# Schematic.net
KiCad netlist of a schematic drawn in EAGLE
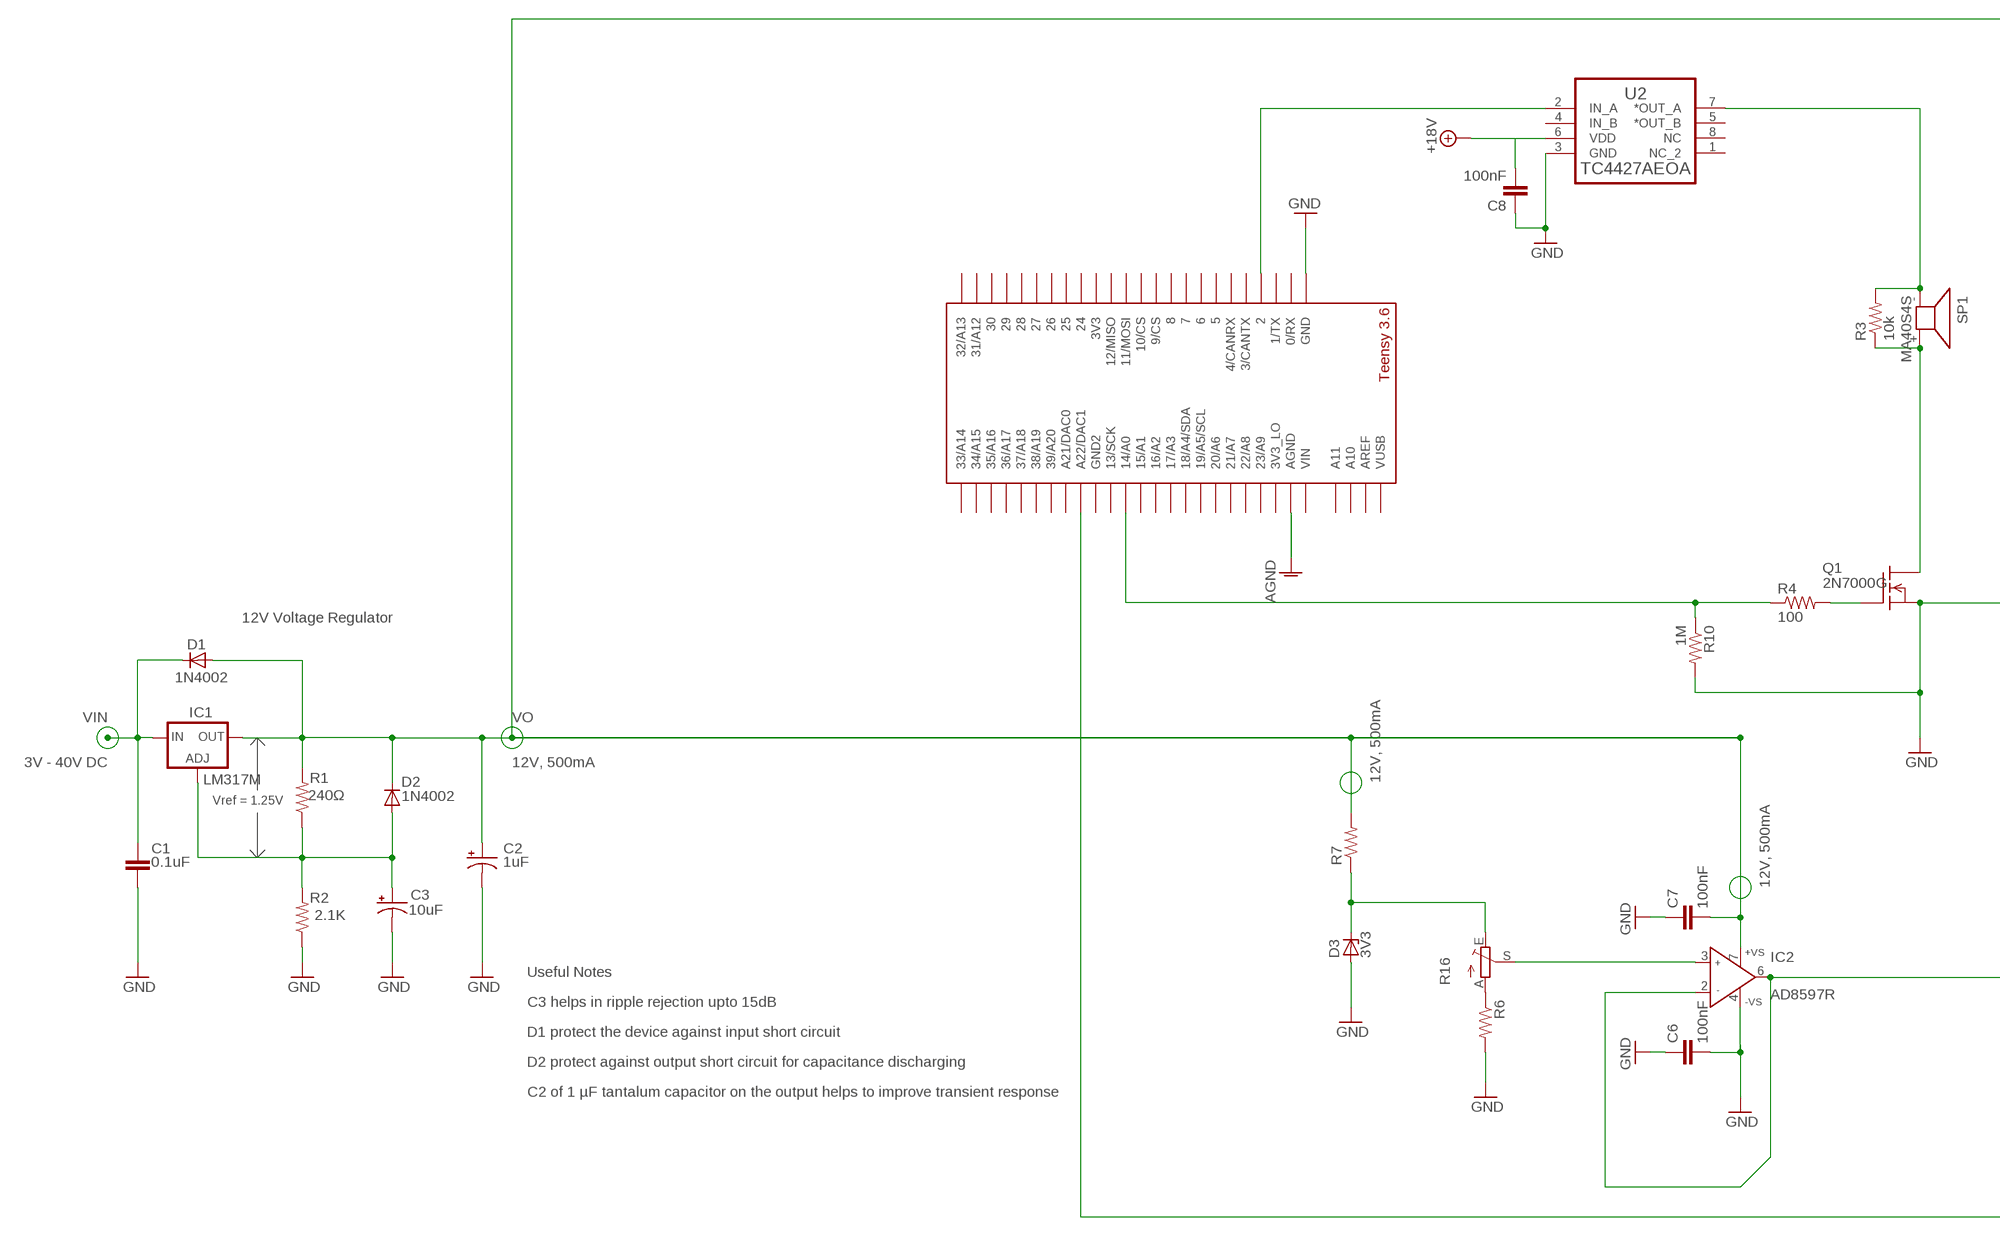
[diagram p0: schematic, sheet 1, part 1 of 2]
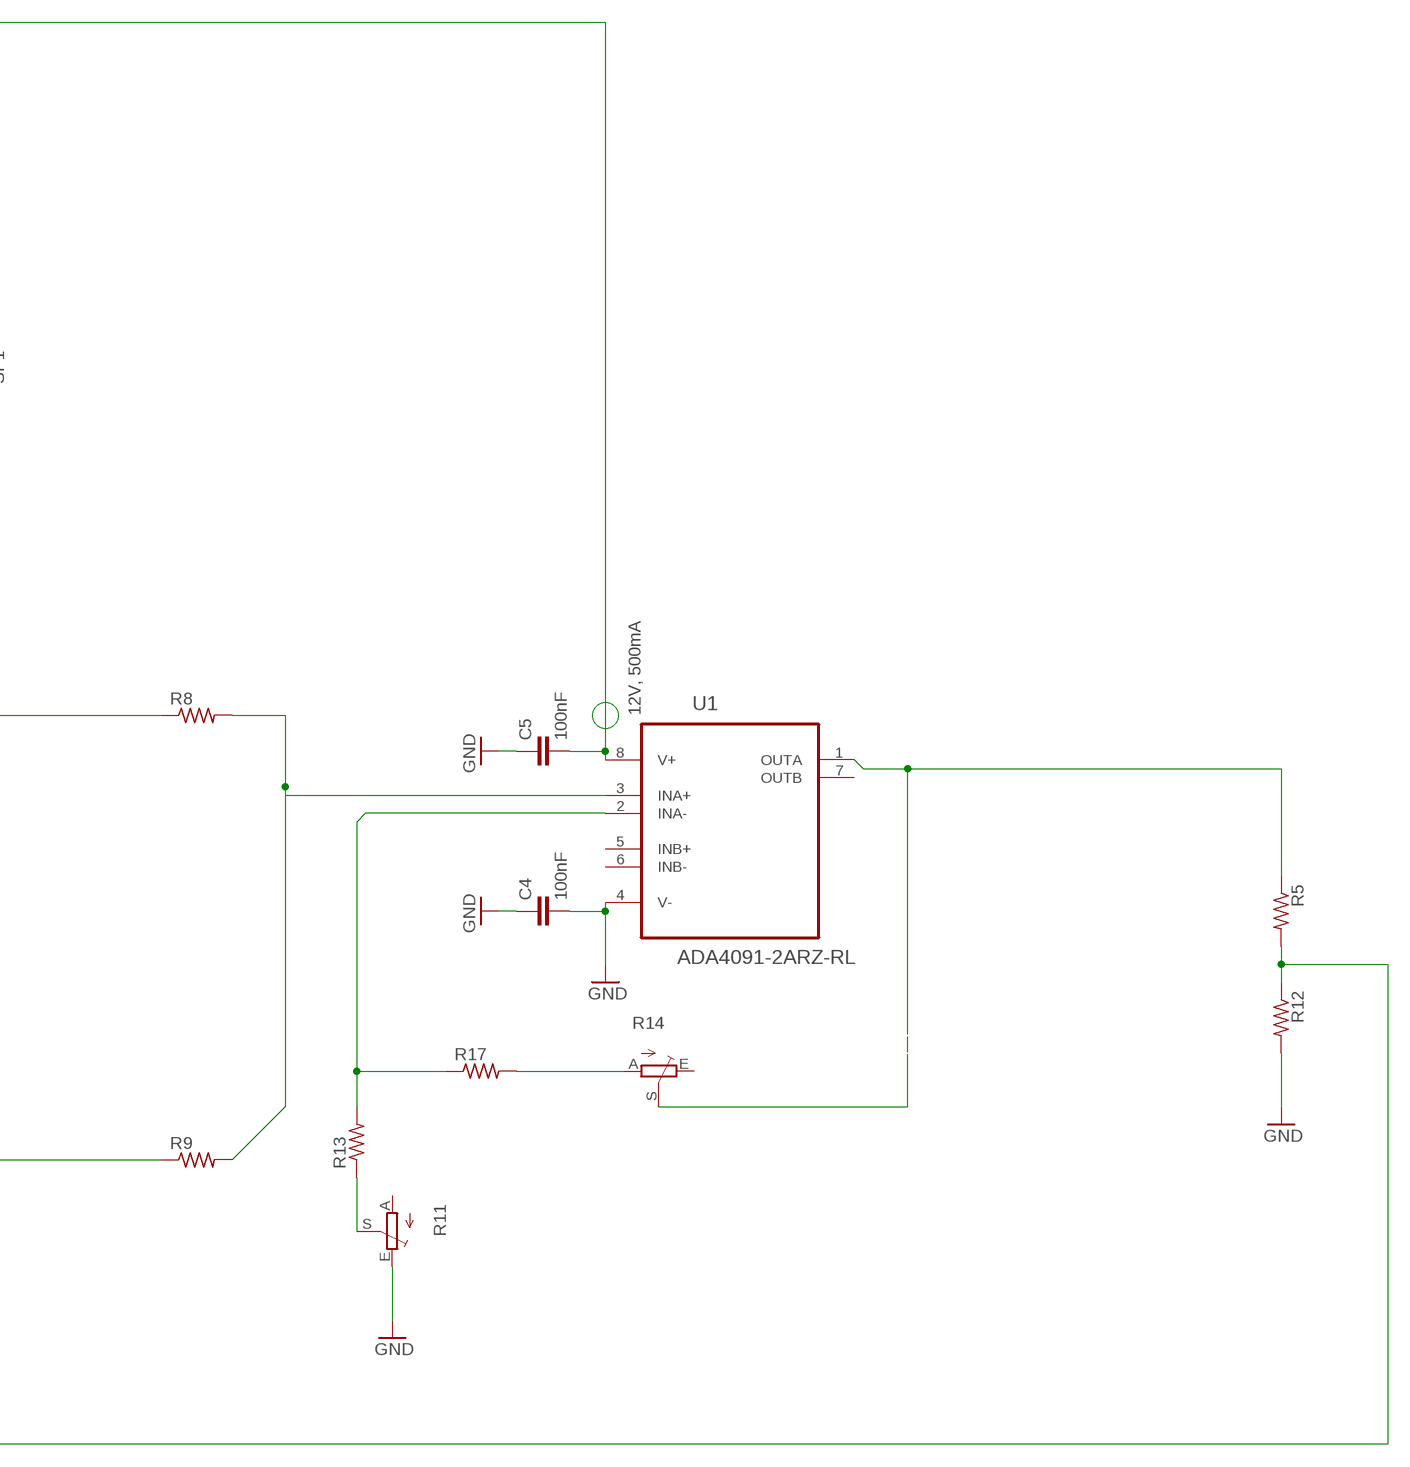
[diagram p1: schematic, sheet 1, part 2 of 2]

(export (version "E")
  (design (tool "Eeschema 10.0.6"))
  (components
    (comp (ref "C1")
      (value "0.1uF")
      (footprint "eagle-import:C075-052X106")
      (libsource (lib "eagle-import") (part "C-EU075-052X106"))
    )
    (comp (ref "C2")
      (value "1uF")
      (footprint "eagle-import:085CS_1AR")
      (libsource (lib "eagle-import") (part "CPOL-US085CS-1AR"))
    )
    (comp (ref "C3")
      (value "10uF")
      (footprint "eagle-import:085CS_1AR")
      (libsource (lib "eagle-import") (part "CPOL-US085CS-1AR"))
    )
    (comp (ref "C4")
      (value "100nF")
      (footprint "eagle-import:C2.5-3")
      (libsource (lib "eagle-import") (part "C2,5-3"))
    )
    (comp (ref "C5")
      (value "100nF")
      (footprint "eagle-import:C2.5-3")
      (libsource (lib "eagle-import") (part "C2,5-3"))
    )
    (comp (ref "C6")
      (value "100nF")
      (footprint "eagle-import:C2.5-3")
      (libsource (lib "eagle-import") (part "C2,5-3"))
    )
    (comp (ref "C7")
      (value "100nF")
      (footprint "eagle-import:C2.5-3")
      (libsource (lib "eagle-import") (part "C2,5-3"))
    )
    (comp (ref "C8")
      (value "100nF")
      (footprint "eagle-import:C2.5-3")
      (libsource (lib "eagle-import") (part "C2,5-3"))
    )
    (comp (ref "D1")
      (value "1N4002")
      (footprint "eagle-import:DO41-10")
      (libsource (lib "eagle-import") (part "1N4004"))
    )
    (comp (ref "D2")
      (value "1N4002")
      (footprint "eagle-import:DO41-10")
      (libsource (lib "eagle-import") (part "1N4004"))
    )
    (comp (ref "D3")
      (value "3V3")
      (footprint "eagle-import:DO41Z10")
      (libsource (lib "eagle-import") (part "1N4728"))
    )
    (comp (ref "IC1")
      (value "LM317MBSTT3")
      (footprint "eagle-import:SOT223")
      (fields (field (name "PARTNUMBER") "LM317M"))
      (libsource (lib "eagle-import") (part "LM317?MBSTT3"))
    )
    (comp (ref "IC2")
      (value "AD8597R")
      (footprint "eagle-import:SO8")
      (fields (field (name "MPN") "AD8597ARZ"))
      (libsource (lib "eagle-import") (part "AD8597R"))
    )
    (comp (ref "Q1")
      (value "2N7000G")
      (footprint "eagle-import:TO92-INLINE")
      (fields (field (name "MF") "Microchip") (field (name "MP") "2N7000-G"))
      (libsource (lib "eagle-import") (part "2N7000G"))
    )
    (comp (ref "R1")
      (value "240Ω")
      (footprint "eagle-import:M0805")
      (libsource (lib "eagle-import") (part "R-US_M0805"))
    )
    (comp (ref "R2")
      (value "2.1K")
      (footprint "eagle-import:M0805")
      (libsource (lib "eagle-import") (part "R-US_M0805"))
    )
    (comp (ref "R3")
      (value "10k")
      (footprint "eagle-import:R0805")
      (libsource (lib "eagle-import") (part "R-US_R0805"))
    )
    (comp (ref "R4")
      (value "100")
      (footprint "eagle-import:M0805")
      (libsource (lib "eagle-import") (part "R-US_M0805"))
    )
    (comp (ref "R5")
      (value "R-US_M0805")
      (footprint "eagle-import:M0805")
      (libsource (lib "eagle-import") (part "R-US_M0805"))
    )
    (comp (ref "R6")
      (value "R-US_M0805")
      (footprint "eagle-import:M0805")
      (libsource (lib "eagle-import") (part "R-US_M0805"))
    )
    (comp (ref "R7")
      (value "R-US_M0805")
      (footprint "eagle-import:M0805")
      (libsource (lib "eagle-import") (part "R-US_M0805"))
    )
    (comp (ref "R8")
      (value "R-US_M0805")
      (footprint "eagle-import:M0805")
      (libsource (lib "eagle-import") (part "R-US_M0805"))
    )
    (comp (ref "R9")
      (value "R-US_M0805")
      (footprint "eagle-import:M0805")
      (libsource (lib "eagle-import") (part "R-US_M0805"))
    )
    (comp (ref "R10")
      (value "1M")
      (footprint "eagle-import:M0805")
      (libsource (lib "eagle-import") (part "R-US_M0805"))
    )
    (comp (ref "R11")
      (value "TRIM_EU-CA6V")
      (footprint "eagle-import:CA6V")
      (libsource (lib "eagle-import") (part "TRIM_EU-CA6V"))
    )
    (comp (ref "R12")
      (value "R-US_M0805")
      (footprint "eagle-import:M0805")
      (libsource (lib "eagle-import") (part "R-US_M0805"))
    )
    (comp (ref "R13")
      (value "R-US_M0805")
      (footprint "eagle-import:M0805")
      (libsource (lib "eagle-import") (part "R-US_M0805"))
    )
    (comp (ref "R14")
      (value "TRIM_EU-CA6V")
      (footprint "eagle-import:CA6V")
      (libsource (lib "eagle-import") (part "TRIM_EU-CA6V"))
    )
    (comp (ref "R16")
      (value "TRIM_EU-CA6V")
      (footprint "eagle-import:CA6V")
      (libsource (lib "eagle-import") (part "TRIM_EU-CA6V"))
    )
    (comp (ref "R17")
      (value "R-US_M0805")
      (footprint "eagle-import:M0805")
      (libsource (lib "eagle-import") (part "R-US_M0805"))
    )
    (comp (ref "SP1")
      (value "MA40S4S")
      (footprint "eagle-import:MA40")
      (libsource (lib "eagle-import") (part "MA40S4S"))
    )
    (comp (ref "U$1")
      (value "TEENSY_3.5/3.6_BASIC")
      (footprint "eagle-import:TEENSY_3.5_3.6_BASIC")
      (libsource (lib "eagle-import") (part "TEENSY_3.5/3.6_BASIC"))
    )
    (comp (ref "U1")
      (value "ADA4091-2ARZ-RL")
      (footprint "eagle-import:SOIC127P600X175-8N")
      (fields (field (name "MF") "Analog"))
      (libsource (lib "eagle-import") (part "ADA4091-2ARZ-RL"))
    )
    (comp (ref "U2")
      (value "TC4427AEOA")
      (footprint "eagle-import:SOIC127P600X175-8N")
      (libsource (lib "eagle-import") (part "TC4427AEOA"))
    )
  )
  (nets
    (net (code "1") (name "+18V") (class "Default")
      (node (ref "U2") (pin "6") (pinfunction "VDD_6") (pintype "power_in"))
    )
    (net (code "2") (name "/VIN") (class "Default")
      (node (ref "C1") (pin "1") (pinfunction "1_1") (pintype "passive"))
      (node (ref "D1") (pin "C") (pinfunction "C_C") (pintype "passive"))
      (node (ref "IC1") (pin "3") (pinfunction "IN_3") (pintype "input"))
    )
    (net (code "3") (name "/VO") (class "Default")
      (node (ref "C2") (pin "+") (pinfunction "+_+") (pintype "passive"))
      (node (ref "C5") (pin "2") (pinfunction "2_2") (pintype "passive"))
      (node (ref "C7") (pin "2") (pinfunction "2_2") (pintype "passive"))
      (node (ref "D1") (pin "A") (pinfunction "A_A") (pintype "passive"))
      (node (ref "D2") (pin "C") (pinfunction "C_C") (pintype "passive"))
      (node (ref "IC1") (pin "4") (pinfunction "OUT_4") (pintype "passive"))
      (node (ref "IC2") (pin "7") (pinfunction "+VS_7") (pintype "input"))
      (node (ref "R1") (pin "2") (pinfunction "2_2") (pintype "passive"))
      (node (ref "R7") (pin "2") (pinfunction "2_2") (pintype "passive"))
      (node (ref "U1") (pin "8") (pinfunction "V+_8") (pintype "power_in"))
    )
    (net (code "4") (name "AGND") (class "Default")
      (node (ref "U$1") (pin "AGND") (pinfunction "AGND_AGND") (pintype "bidirectional"))
    )
    (net (code "5") (name "GND") (class "Default")
      (node (ref "C1") (pin "2") (pinfunction "2_2") (pintype "passive"))
      (node (ref "C2") (pin "-") (pinfunction "-_-") (pintype "passive"))
      (node (ref "C3") (pin "-") (pinfunction "-_-") (pintype "passive"))
      (node (ref "C4") (pin "1") (pinfunction "1_1") (pintype "passive"))
      (node (ref "C4") (pin "2") (pinfunction "2_2") (pintype "passive"))
      (node (ref "C5") (pin "1") (pinfunction "1_1") (pintype "passive"))
      (node (ref "C6") (pin "1") (pinfunction "1_1") (pintype "passive"))
      (node (ref "C6") (pin "2") (pinfunction "2_2") (pintype "passive"))
      (node (ref "C7") (pin "1") (pinfunction "1_1") (pintype "passive"))
      (node (ref "C8") (pin "1") (pinfunction "1_1") (pintype "passive"))
      (node (ref "D3") (pin "A") (pinfunction "A_A") (pintype "passive"))
      (node (ref "IC2") (pin "4") (pinfunction "-VS_4") (pintype "input"))
      (node (ref "Q1") (pin "1") (pinfunction "SRC_1") (pintype "passive"))
      (node (ref "R10") (pin "2") (pinfunction "2_2") (pintype "passive"))
      (node (ref "R11") (pin "E") (pinfunction "E_E") (pintype "passive"))
      (node (ref "R12") (pin "2") (pinfunction "2_2") (pintype "passive"))
      (node (ref "R2") (pin "1") (pinfunction "1_1") (pintype "passive"))
      (node (ref "R6") (pin "2") (pinfunction "2_2") (pintype "passive"))
      (node (ref "R8") (pin "1") (pinfunction "1_1") (pintype "passive"))
      (node (ref "U$1") (pin "GND") (pinfunction "GND_GND") (pintype "bidirectional"))
      (node (ref "U1") (pin "4") (pinfunction "V-_4") (pintype "power_in"))
      (node (ref "U2") (pin "3") (pinfunction "GND_3") (pintype "passive"))
    )
    (net (code "6") (name "Net-(D3-PadC)") (class "Default")
      (node (ref "D3") (pin "C") (pinfunction "C_C") (pintype "passive"))
      (node (ref "R16") (pin "E") (pinfunction "E_E") (pintype "passive"))
      (node (ref "R7") (pin "1") (pinfunction "1_1") (pintype "passive"))
    )
    (net (code "7") (name "Net-(IC1-ADJ)") (class "Default")
      (node (ref "C3") (pin "+") (pinfunction "+_+") (pintype "passive"))
      (node (ref "D2") (pin "A") (pinfunction "A_A") (pintype "passive"))
      (node (ref "IC1") (pin "1") (pinfunction "ADJ_1") (pintype "input"))
      (node (ref "R1") (pin "1") (pinfunction "1_1") (pintype "passive"))
      (node (ref "R2") (pin "2") (pinfunction "2_2") (pintype "passive"))
    )
    (net (code "8") (name "Net-(IC2-IN+)") (class "Default")
      (node (ref "IC2") (pin "3") (pinfunction "IN+_3") (pintype "input"))
      (node (ref "R16") (pin "S") (pinfunction "S_S") (pintype "passive"))
    )
    (net (code "9") (name "Net-(IC2-IN-)") (class "Default")
      (node (ref "IC2") (pin "2") (pinfunction "IN-_2") (pintype "input"))
      (node (ref "IC2") (pin "6") (pinfunction "OUT_6") (pintype "output"))
      (node (ref "R9") (pin "1") (pinfunction "1_1") (pintype "passive"))
    )
    (net (code "10") (name "Net-(Q1-DRN)") (class "Default")
      (node (ref "Q1") (pin "3") (pinfunction "DRN_3") (pintype "passive"))
      (node (ref "R3") (pin "1") (pinfunction "1_1") (pintype "passive"))
      (node (ref "SP1") (pin "+") (pinfunction "2_+") (pintype "passive"))
    )
    (net (code "11") (name "Net-(Q1-GATE)") (class "Default")
      (node (ref "Q1") (pin "2") (pinfunction "GATE_2") (pintype "passive"))
      (node (ref "R4") (pin "2") (pinfunction "2_2") (pintype "passive"))
    )
    (net (code "12") (name "Net-(R10-Pad1)") (class "Default")
      (node (ref "R10") (pin "1") (pinfunction "1_1") (pintype "passive"))
      (node (ref "R4") (pin "1") (pinfunction "1_1") (pintype "passive"))
      (node (ref "U$1") (pin "14/A0") (pinfunction "14/A0_14/A0") (pintype "bidirectional"))
    )
    (net (code "13") (name "Net-(R11-PadS)") (class "Default")
      (node (ref "R11") (pin "S") (pinfunction "S_S") (pintype "passive"))
      (node (ref "R13") (pin "1") (pinfunction "1_1") (pintype "passive"))
    )
    (net (code "14") (name "Net-(R12-Pad1)") (class "Default")
      (node (ref "R12") (pin "1") (pinfunction "1_1") (pintype "passive"))
      (node (ref "R5") (pin "2") (pinfunction "2_2") (pintype "passive"))
      (node (ref "U$1") (pin "A22/DAC1") (pinfunction "A22/DAC1_A22/DAC1") (pintype "bidirectional"))
    )
    (net (code "15") (name "Net-(R14-PadA)") (class "Default")
      (node (ref "R14") (pin "A") (pinfunction "A_A") (pintype "passive"))
      (node (ref "R17") (pin "2") (pinfunction "2_2") (pintype "passive"))
    )
    (net (code "16") (name "Net-(R16-PadA)") (class "Default")
      (node (ref "R16") (pin "A") (pinfunction "A_A") (pintype "passive"))
      (node (ref "R6") (pin "1") (pinfunction "1_1") (pintype "passive"))
    )
    (net (code "17") (name "Net-(SP1-1)") (class "Default")
      (node (ref "R3") (pin "2") (pinfunction "2_2") (pintype "passive"))
      (node (ref "SP1") (pin "-") (pinfunction "1_-") (pintype "passive"))
      (node (ref "U2") (pin "7") (pinfunction "*OUT_A_7") (pintype "output"))
    )
    (net (code "18") (name "Net-(U1-INA+)") (class "Default")
      (node (ref "R8") (pin "2") (pinfunction "2_2") (pintype "passive"))
      (node (ref "R9") (pin "2") (pinfunction "2_2") (pintype "passive"))
      (node (ref "U1") (pin "3") (pinfunction "INA+_3") (pintype "input"))
    )
    (net (code "19") (name "Net-(U1-INA-)") (class "Default")
      (node (ref "R13") (pin "2") (pinfunction "2_2") (pintype "passive"))
      (node (ref "R17") (pin "1") (pinfunction "1_1") (pintype "passive"))
      (node (ref "U1") (pin "2") (pinfunction "INA-_2") (pintype "input"))
    )
    (net (code "20") (name "Net-(U1-OUTA)") (class "Default")
      (node (ref "R5") (pin "1") (pinfunction "1_1") (pintype "passive"))
      (node (ref "U1") (pin "1") (pinfunction "OUTA_1") (pintype "output"))
    )
    (net (code "21") (name "Net-(U2-IN_A)") (class "Default")
      (node (ref "U$1") (pin "2") (pinfunction "2_2") (pintype "bidirectional"))
      (node (ref "U2") (pin "2") (pinfunction "IN_A_2") (pintype "input"))
    )
    (net (code "22") (name "unconnected-(C8-Pad2)") (class "Default")
      (node (ref "C8") (pin "2") (pinfunction "2_2") (pintype "passive"))
    )
    (net (code "23") (name "unconnected-(R11-PadA)") (class "Default")
      (node (ref "R11") (pin "A") (pinfunction "A_A") (pintype "passive"))
    )
    (net (code "24") (name "unconnected-(R14-PadE)") (class "Default")
      (node (ref "R14") (pin "E") (pinfunction "E_E") (pintype "passive"))
    )
    (net (code "25") (name "unconnected-(R14-PadS)") (class "Default")
      (node (ref "R14") (pin "S") (pinfunction "S_S") (pintype "passive"))
    )
    (net (code "26") (name "unconnected-(U$1-A21{slash}DAC0-Pad21{slash}DAC0)") (class "Default")
      (node (ref "U$1") (pin "21/DAC0") (pinfunction "A21/DAC0_21/DAC0") (pintype "bidirectional"))
    )
    (net (code "27") (name "unconnected-(U$1-Pad0{slash}RX)") (class "Default")
      (node (ref "U$1") (pin "0/RX") (pinfunction "0/RX_0/RX") (pintype "bidirectional"))
    )
    (net (code "28") (name "unconnected-(U$1-Pad1{slash}TX)") (class "Default")
      (node (ref "U$1") (pin "1/TX") (pinfunction "1/TX_1/TX") (pintype "bidirectional"))
    )
    (net (code "29") (name "unconnected-(U$1-Pad3V3)") (class "Default")
      (node (ref "U$1") (pin "3V3") (pinfunction "3V3_3V3") (pintype "bidirectional"))
    )
    (net (code "30") (name "unconnected-(U$1-Pad3V3_LO)") (class "Default")
      (node (ref "U$1") (pin "3V3_LO") (pinfunction "3V3_LO_3V3_LO") (pintype "bidirectional"))
    )
    (net (code "31") (name "unconnected-(U$1-Pad3{slash}CANTX)") (class "Default")
      (node (ref "U$1") (pin "3/CANTX") (pinfunction "3/CANTX_3/CANTX") (pintype "bidirectional"))
    )
    (net (code "32") (name "unconnected-(U$1-Pad4{slash}CANRX)") (class "Default")
      (node (ref "U$1") (pin "4/CANRX") (pinfunction "4/CANRX_4/CANRX") (pintype "bidirectional"))
    )
    (net (code "33") (name "unconnected-(U$1-Pad5)") (class "Default")
      (node (ref "U$1") (pin "5") (pinfunction "5_5") (pintype "bidirectional"))
    )
    (net (code "34") (name "unconnected-(U$1-Pad6)") (class "Default")
      (node (ref "U$1") (pin "6") (pinfunction "6_6") (pintype "bidirectional"))
    )
    (net (code "35") (name "unconnected-(U$1-Pad7)") (class "Default")
      (node (ref "U$1") (pin "7") (pinfunction "7_7") (pintype "bidirectional"))
    )
    (net (code "36") (name "unconnected-(U$1-Pad8)") (class "Default")
      (node (ref "U$1") (pin "8") (pinfunction "8_8") (pintype "bidirectional"))
    )
    (net (code "37") (name "unconnected-(U$1-Pad9{slash}CS)") (class "Default")
      (node (ref "U$1") (pin "9/CS") (pinfunction "9/CS_9/CS") (pintype "bidirectional"))
    )
    (net (code "38") (name "unconnected-(U$1-Pad10{slash}CS)") (class "Default")
      (node (ref "U$1") (pin "10/CS") (pinfunction "10/CS_10/CS") (pintype "bidirectional"))
    )
    (net (code "39") (name "unconnected-(U$1-Pad11{slash}MOSI)") (class "Default")
      (node (ref "U$1") (pin "11/MOSI") (pinfunction "11/MOSI_11/MOSI") (pintype "bidirectional"))
    )
    (net (code "40") (name "unconnected-(U$1-Pad12{slash}MISO)") (class "Default")
      (node (ref "U$1") (pin "12/MISO") (pinfunction "12/MISO_12/MISO") (pintype "bidirectional"))
    )
    (net (code "41") (name "unconnected-(U$1-Pad13{slash}SCK)") (class "Default")
      (node (ref "U$1") (pin "13/SCK") (pinfunction "13/SCK_13/SCK") (pintype "bidirectional"))
    )
    (net (code "42") (name "unconnected-(U$1-Pad15{slash}A1)") (class "Default")
      (node (ref "U$1") (pin "15/A1") (pinfunction "15/A1_15/A1") (pintype "bidirectional"))
    )
    (net (code "43") (name "unconnected-(U$1-Pad16{slash}A2)") (class "Default")
      (node (ref "U$1") (pin "16/A2") (pinfunction "16/A2_16/A2") (pintype "bidirectional"))
    )
    (net (code "44") (name "unconnected-(U$1-Pad17{slash}A3)") (class "Default")
      (node (ref "U$1") (pin "17/A3") (pinfunction "17/A3_17/A3") (pintype "bidirectional"))
    )
    (net (code "45") (name "unconnected-(U$1-Pad18{slash}A4{slash}SDA)") (class "Default")
      (node (ref "U$1") (pin "18/A4/SDA") (pinfunction "18/A4/SDA_18/A4/SDA") (pintype "bidirectional"))
    )
    (net (code "46") (name "unconnected-(U$1-Pad19{slash}A5{slash}SCL)") (class "Default")
      (node (ref "U$1") (pin "19/A5/SCL") (pinfunction "19/A5/SCL_19/A5/SCL") (pintype "bidirectional"))
    )
    (net (code "47") (name "unconnected-(U$1-Pad20{slash}A6)") (class "Default")
      (node (ref "U$1") (pin "20/A6") (pinfunction "20/A6_20/A6") (pintype "bidirectional"))
    )
    (net (code "48") (name "unconnected-(U$1-Pad21{slash}A7)") (class "Default")
      (node (ref "U$1") (pin "21/A7") (pinfunction "21/A7_21/A7") (pintype "bidirectional"))
    )
    (net (code "49") (name "unconnected-(U$1-Pad22{slash}A8)") (class "Default")
      (node (ref "U$1") (pin "22/A8") (pinfunction "22/A8_22/A8") (pintype "bidirectional"))
    )
    (net (code "50") (name "unconnected-(U$1-Pad23{slash}A9)") (class "Default")
      (node (ref "U$1") (pin "23/A9") (pinfunction "23/A9_23/A9") (pintype "bidirectional"))
    )
    (net (code "51") (name "unconnected-(U$1-Pad24)") (class "Default")
      (node (ref "U$1") (pin "24") (pinfunction "24_24") (pintype "bidirectional"))
    )
    (net (code "52") (name "unconnected-(U$1-Pad25)") (class "Default")
      (node (ref "U$1") (pin "25") (pinfunction "25_25") (pintype "bidirectional"))
    )
    (net (code "53") (name "unconnected-(U$1-Pad26)") (class "Default")
      (node (ref "U$1") (pin "26") (pinfunction "26_26") (pintype "bidirectional"))
    )
    (net (code "54") (name "unconnected-(U$1-Pad27)") (class "Default")
      (node (ref "U$1") (pin "27") (pinfunction "27_27") (pintype "bidirectional"))
    )
    (net (code "55") (name "unconnected-(U$1-Pad28)") (class "Default")
      (node (ref "U$1") (pin "28") (pinfunction "28_28") (pintype "bidirectional"))
    )
    (net (code "56") (name "unconnected-(U$1-Pad29)") (class "Default")
      (node (ref "U$1") (pin "29") (pinfunction "29_29") (pintype "bidirectional"))
    )
    (net (code "57") (name "unconnected-(U$1-Pad30)") (class "Default")
      (node (ref "U$1") (pin "30") (pinfunction "30_30") (pintype "bidirectional"))
    )
    (net (code "58") (name "unconnected-(U$1-Pad31{slash}A12)") (class "Default")
      (node (ref "U$1") (pin "31/A12") (pinfunction "31/A12_31/A12") (pintype "bidirectional"))
    )
    (net (code "59") (name "unconnected-(U$1-Pad32{slash}A13)") (class "Default")
      (node (ref "U$1") (pin "32/A13") (pinfunction "32/A13_32/A13") (pintype "bidirectional"))
    )
    (net (code "60") (name "unconnected-(U$1-Pad33{slash}A14)") (class "Default")
      (node (ref "U$1") (pin "33/A14") (pinfunction "33/A14_33/A14") (pintype "bidirectional"))
    )
    (net (code "61") (name "unconnected-(U$1-Pad34{slash}A15)") (class "Default")
      (node (ref "U$1") (pin "34/A15") (pinfunction "34/A15_34/A15") (pintype "bidirectional"))
    )
    (net (code "62") (name "unconnected-(U$1-Pad35{slash}A16)") (class "Default")
      (node (ref "U$1") (pin "35/A16") (pinfunction "35/A16_35/A16") (pintype "bidirectional"))
    )
    (net (code "63") (name "unconnected-(U$1-Pad36{slash}A17)") (class "Default")
      (node (ref "U$1") (pin "36/A17") (pinfunction "36/A17_36/A17") (pintype "bidirectional"))
    )
    (net (code "64") (name "unconnected-(U$1-Pad37{slash}A18)") (class "Default")
      (node (ref "U$1") (pin "37/A18") (pinfunction "37/A18_37/A18") (pintype "bidirectional"))
    )
    (net (code "65") (name "unconnected-(U$1-Pad38{slash}A19)") (class "Default")
      (node (ref "U$1") (pin "38/A19") (pinfunction "38/A19_38/A19") (pintype "bidirectional"))
    )
    (net (code "66") (name "unconnected-(U$1-Pad39{slash}A20)") (class "Default")
      (node (ref "U$1") (pin "39/A20") (pinfunction "39/A20_39/A20") (pintype "bidirectional"))
    )
    (net (code "67") (name "unconnected-(U$1-PadA10)") (class "Default")
      (node (ref "U$1") (pin "A10") (pinfunction "A10_A10") (pintype "bidirectional"))
    )
    (net (code "68") (name "unconnected-(U$1-PadA11)") (class "Default")
      (node (ref "U$1") (pin "A11") (pinfunction "A11_A11") (pintype "bidirectional"))
    )
    (net (code "69") (name "unconnected-(U$1-PadAREF)") (class "Default")
      (node (ref "U$1") (pin "AREF") (pinfunction "AREF_AREF") (pintype "bidirectional"))
    )
    (net (code "70") (name "unconnected-(U$1-PadGND2)") (class "Default")
      (node (ref "U$1") (pin "GND2") (pinfunction "GND2_GND2") (pintype "bidirectional"))
    )
    (net (code "71") (name "unconnected-(U$1-PadVIN)") (class "Default")
      (node (ref "U$1") (pin "VIN") (pinfunction "VIN_VIN") (pintype "bidirectional"))
    )
    (net (code "72") (name "unconnected-(U$1-PadVUSB)") (class "Default")
      (node (ref "U$1") (pin "VUSB") (pinfunction "VUSB_VUSB") (pintype "bidirectional"))
    )
    (net (code "73") (name "unconnected-(U1-INB+-Pad5)") (class "Default")
      (node (ref "U1") (pin "5") (pinfunction "INB+_5") (pintype "input"))
    )
    (net (code "74") (name "unconnected-(U1-INB--Pad6)") (class "Default")
      (node (ref "U1") (pin "6") (pinfunction "INB-_6") (pintype "input"))
    )
    (net (code "75") (name "unconnected-(U1-OUTB-Pad7)") (class "Default")
      (node (ref "U1") (pin "7") (pinfunction "OUTB_7") (pintype "output"))
    )
    (net (code "76") (name "unconnected-(U2-*OUT_B-Pad5)") (class "Default")
      (node (ref "U2") (pin "5") (pinfunction "*OUT_B_5") (pintype "output"))
    )
    (net (code "77") (name "unconnected-(U2-IN_B-Pad4)") (class "Default")
      (node (ref "U2") (pin "4") (pinfunction "IN_B_4") (pintype "input"))
    )
    (net (code "78") (name "unconnected-(U2-NC-Pad8)") (class "Default")
      (node (ref "U2") (pin "8") (pinfunction "NC_8") (pintype "no_connect"))
    )
    (net (code "79") (name "unconnected-(U2-NC_2-Pad1)") (class "Default")
      (node (ref "U2") (pin "1") (pinfunction "NC_2_1") (pintype "no_connect"))
    )
  )
)
